# neopixelwordclock.net
KiCad netlist of a schematic drawn in EAGLE
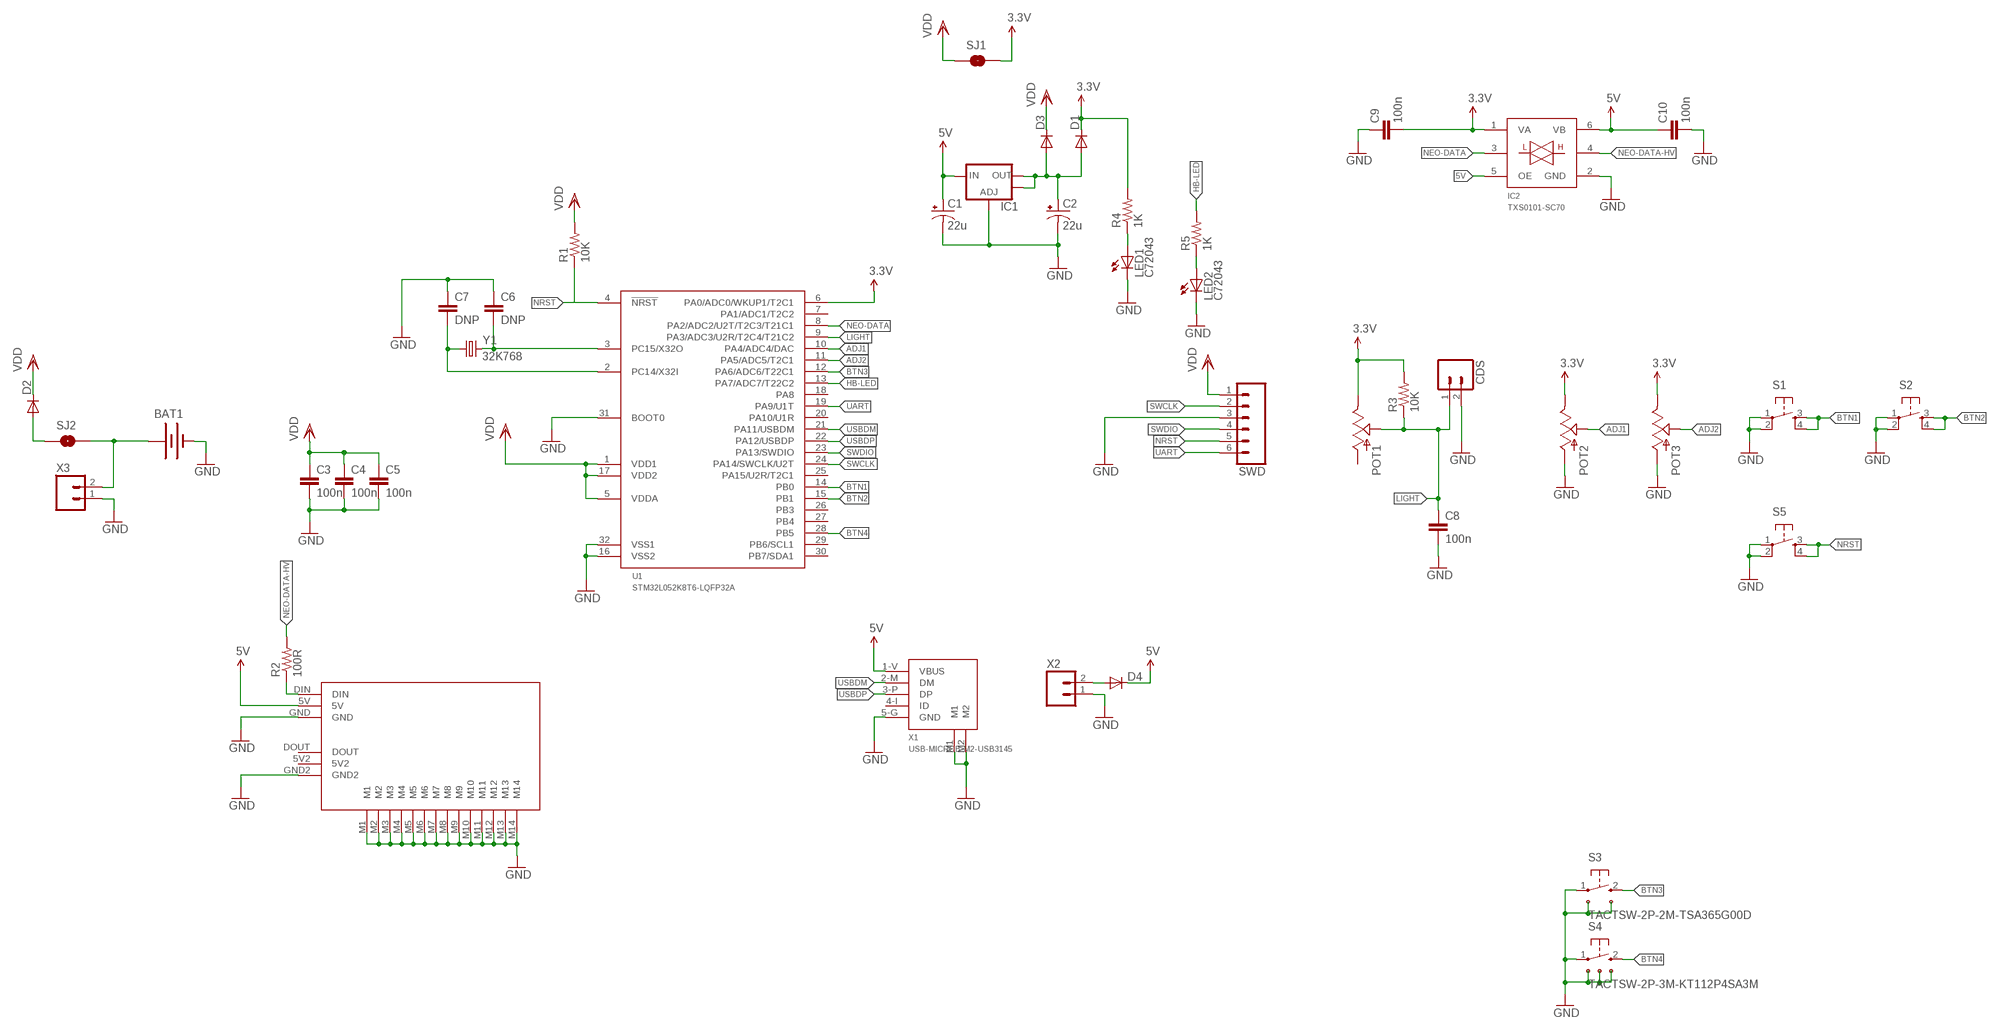
[diagram p0: schematic, sheet 1]

(export (version "E")
  (design (tool "Eeschema 10.0.6"))
  (components
    (comp (ref "BAT1")
      (value "BATTERY-JLC")
      (footprint "eagle-import:BATT-COIN-CR2032-BS-6-1")
      (libsource (lib "eagle-import") (part "BATTERY-JLC"))
    )
    (comp (ref "C1")
      (value "22u")
      (footprint "eagle-import:EIA3528")
      (libsource (lib "eagle-import") (part "CAP_POL3528"))
    )
    (comp (ref "C2")
      (value "22u")
      (footprint "eagle-import:EIA3528")
      (libsource (lib "eagle-import") (part "CAP_POL3528"))
    )
    (comp (ref "C3")
      (value "100n")
      (footprint "eagle-import:0603-CAP")
      (libsource (lib "eagle-import") (part "CAP0603-CAP"))
    )
    (comp (ref "C4")
      (value "100n")
      (footprint "eagle-import:0603-CAP")
      (libsource (lib "eagle-import") (part "CAP0603-CAP"))
    )
    (comp (ref "C5")
      (value "100n")
      (footprint "eagle-import:0603-CAP")
      (libsource (lib "eagle-import") (part "CAP0603-CAP"))
    )
    (comp (ref "C6")
      (value "DNP")
      (footprint "eagle-import:0603-CAP")
      (libsource (lib "eagle-import") (part "CAP0603-CAP"))
    )
    (comp (ref "C7")
      (value "DNP")
      (footprint "eagle-import:0603-CAP")
      (libsource (lib "eagle-import") (part "CAP0603-CAP"))
    )
    (comp (ref "C8")
      (value "100n")
      (footprint "eagle-import:0603-CAP")
      (libsource (lib "eagle-import") (part "CAP0603-CAP"))
    )
    (comp (ref "C9")
      (value "100n")
      (footprint "eagle-import:0603-CAP")
      (libsource (lib "eagle-import") (part "CAP0603-CAP"))
    )
    (comp (ref "C10")
      (value "100n")
      (footprint "eagle-import:0603-CAP")
      (libsource (lib "eagle-import") (part "CAP0603-CAP"))
    )
    (comp (ref "CDS")
      (value "M02PTH")
      (footprint "eagle-import:1X02")
      (libsource (lib "eagle-import") (part "M02PTH"))
    )
    (comp (ref "D1")
      (value "DIODESOD")
      (footprint "eagle-import:SOD-323")
      (libsource (lib "eagle-import") (part "DIODESOD"))
    )
    (comp (ref "D2")
      (value "DIODESOD")
      (footprint "eagle-import:SOD-323")
      (libsource (lib "eagle-import") (part "DIODESOD"))
    )
    (comp (ref "D3")
      (value "DIODESOD")
      (footprint "eagle-import:SOD-323")
      (libsource (lib "eagle-import") (part "DIODESOD"))
    )
    (comp (ref "D4")
      (value "DIODESMA")
      (footprint "eagle-import:SMA-DIODE")
      (libsource (lib "eagle-import") (part "DIODESMA"))
    )
    (comp (ref "IC1")
      (value "V_REG_LM1117SOT223")
      (footprint "eagle-import:SOT223")
      (libsource (lib "eagle-import") (part "V_REG_LM1117SOT223"))
    )
    (comp (ref "IC2")
      (value "TXS0101-SC70")
      (footprint "eagle-import:SC70-6")
      (libsource (lib "eagle-import") (part "TXS0101-SC70"))
    )
    (comp (ref "LED1")
      (value "C72043")
      (footprint "eagle-import:LED-0603")
      (libsource (lib "eagle-import") (part "LED0603"))
    )
    (comp (ref "LED2")
      (value "C72043")
      (footprint "eagle-import:LED-0603")
      (libsource (lib "eagle-import") (part "LED0603"))
    )
    (comp (ref "POT1")
      (value "POT-SMD-A")
      (footprint "eagle-import:POT-SMD")
      (libsource (lib "eagle-import") (part "POT-SMD-A"))
    )
    (comp (ref "POT2")
      (value "POT-SMD-A")
      (footprint "eagle-import:POT-SMD")
      (libsource (lib "eagle-import") (part "POT-SMD-A"))
    )
    (comp (ref "POT3")
      (value "POT-SMD-A")
      (footprint "eagle-import:POT-SMD")
      (libsource (lib "eagle-import") (part "POT-SMD-A"))
    )
    (comp (ref "R1")
      (value "10K")
      (footprint "eagle-import:0603-RES")
      (libsource (lib "eagle-import") (part "RESISTOR0603-RES"))
    )
    (comp (ref "R2")
      (value "100R")
      (footprint "eagle-import:0603-RES")
      (libsource (lib "eagle-import") (part "RESISTOR0603-RES"))
    )
    (comp (ref "R3")
      (value "10K")
      (footprint "eagle-import:0603-RES")
      (libsource (lib "eagle-import") (part "RESISTOR0603-RES"))
    )
    (comp (ref "R4")
      (value "1K")
      (footprint "eagle-import:0603-RES")
      (libsource (lib "eagle-import") (part "RESISTOR0603-RES"))
    )
    (comp (ref "R5")
      (value "1K")
      (footprint "eagle-import:0603-RES")
      (libsource (lib "eagle-import") (part "RESISTOR0603-RES"))
    )
    (comp (ref "S1")
      (value "TAC_SWITCHSMD")
      (footprint "eagle-import:TACTILE_SWITCH_SMD")
      (libsource (lib "eagle-import") (part "TAC_SWITCHSMD"))
    )
    (comp (ref "S2")
      (value "TAC_SWITCHSMD")
      (footprint "eagle-import:TACTILE_SWITCH_SMD")
      (libsource (lib "eagle-import") (part "TAC_SWITCHSMD"))
    )
    (comp (ref "S3")
      (value "TACTSW-2P-2M-TSA365G00D")
      (footprint "eagle-import:TACTSW-SMD-SIDE-TSA365G00D")
      (libsource (lib "eagle-import") (part "TACTSW-2P-2M-TSA365G00D"))
    )
    (comp (ref "S4")
      (value "TACTSW-2P-3M-KT112P4SA3M")
      (footprint "eagle-import:TACTSW-SMD-SIDE-KT11P4SA3M")
      (libsource (lib "eagle-import") (part "TACTSW-2P-3M-KT112P4SA3M"))
    )
    (comp (ref "S5")
      (value "TAC_SWITCHSMD")
      (footprint "eagle-import:TACTILE_SWITCH_SMD")
      (libsource (lib "eagle-import") (part "TAC_SWITCHSMD"))
    )
    (comp (ref "SJ1")
      (value "SOLDERJUMPERNO")
      (footprint "eagle-import:SJ_2S-NO")
      (libsource (lib "eagle-import") (part "SOLDERJUMPERNO"))
    )
    (comp (ref "SJ2")
      (value "SOLDERJUMPER-BIG")
      (footprint "eagle-import:SJ_2S_BIG")
      (libsource (lib "eagle-import") (part "SOLDERJUMPER-BIG"))
    )
    (comp (ref "SWD")
      (value "M06FEMALE_LOCK")
      (footprint "eagle-import:1X06_FEMALE_LOCK.010")
      (libsource (lib "eagle-import") (part "M06FEMALE_LOCK"))
    )
    (comp (ref "U$1")
      (value "PCB-OUTLINE")
      (footprint "eagle-import:PCB-OUTLINE")
      (libsource (lib "eagle-import") (part "PCB-OUTLINE"))
    )
    (comp (ref "U1")
      (value "STM32L052K8T6-LQFP32A")
      (footprint "eagle-import:LQFP32")
      (libsource (lib "eagle-import") (part "STM32L052K8T6-LQFP32A"))
    )
    (comp (ref "X1")
      (value "USB-MICROB-M2-USB3145")
      (footprint "eagle-import:USBMICROBVERT-USB3145")
      (libsource (lib "eagle-import") (part "USB-MICROB-M2-USB3145"))
    )
    (comp (ref "X2")
      (value "M02-JST-2-PTH-NO_SILK")
      (footprint "eagle-import:JST-2-PTH-NS")
      (libsource (lib "eagle-import") (part "M02-JST-2-PTH-NO_SILK"))
    )
    (comp (ref "X3")
      (value "M02-JST-2-PTH-NO_SILK")
      (footprint "eagle-import:JST-2-PTH-NS")
      (libsource (lib "eagle-import") (part "M02-JST-2-PTH-NO_SILK"))
    )
    (comp (ref "Y1")
      (value "32K768")
      (footprint "eagle-import:XTAL-3.2X1.5")
      (libsource (lib "eagle-import") (part "CRYSTAL-3.2X1.5"))
    )
  )
  (nets
    (net (code "1") (name "3.3V") (class "Default")
      (node (ref "C9") (pin "2") (pinfunction "2_2") (pintype "passive"))
      (node (ref "D1") (pin "1") (pinfunction "C_1") (pintype "passive"))
      (node (ref "IC2") (pin "1") (pinfunction "VA_1") (pintype "input"))
      (node (ref "POT1") (pin "A") (pinfunction "B_A") (pintype "passive"))
      (node (ref "POT2") (pin "A") (pinfunction "B_A") (pintype "passive"))
      (node (ref "POT3") (pin "A") (pinfunction "B_A") (pintype "passive"))
      (node (ref "R3") (pin "2") (pinfunction "2_2") (pintype "passive"))
      (node (ref "R4") (pin "2") (pinfunction "2_2") (pintype "passive"))
      (node (ref "SJ1") (pin "2") (pinfunction "2_2") (pintype "passive"))
      (node (ref "U1") (pin "6") (pinfunction "PA0/ADC0/WKUP1/T2C1_6") (pintype "bidirectional"))
    )
    (net (code "2") (name "5V") (class "Default")
      (node (ref "C1") (pin "A") (pinfunction "+_A") (pintype "passive"))
      (node (ref "C10") (pin "1") (pinfunction "1_1") (pintype "passive"))
      (node (ref "D4") (pin "C") (pinfunction "C_C") (pintype "passive"))
      (node (ref "IC1") (pin "3") (pinfunction "IN_3") (pintype "input"))
      (node (ref "IC2") (pin "5") (pinfunction "OE_5") (pintype "input"))
      (node (ref "IC2") (pin "6") (pinfunction "VB_6") (pintype "input"))
      (node (ref "U$1") (pin "5V") (pinfunction "5V_5V") (pintype "bidirectional"))
      (node (ref "X1") (pin "1-V") (pinfunction "VBUS_1-V") (pintype "bidirectional"))
    )
    (net (code "3") (name "ADJ1") (class "Default")
      (node (ref "POT2") (pin "W") (pinfunction "W_W") (pintype "passive"))
      (node (ref "U1") (pin "10") (pinfunction "PA4/ADC4/DAC_10") (pintype "bidirectional"))
    )
    (net (code "4") (name "ADJ2") (class "Default")
      (node (ref "POT3") (pin "W") (pinfunction "W_W") (pintype "passive"))
      (node (ref "U1") (pin "11") (pinfunction "PA5/ADC5/T2C1_11") (pintype "bidirectional"))
    )
    (net (code "5") (name "BTN1") (class "Default")
      (node (ref "S1") (pin "3") (pinfunction "3_3") (pintype "passive"))
      (node (ref "S1") (pin "4") (pinfunction "4_4") (pintype "passive"))
      (node (ref "U1") (pin "14") (pinfunction "PB0_14") (pintype "bidirectional"))
    )
    (net (code "6") (name "BTN2") (class "Default")
      (node (ref "S2") (pin "3") (pinfunction "3_3") (pintype "passive"))
      (node (ref "S2") (pin "4") (pinfunction "4_4") (pintype "passive"))
      (node (ref "U1") (pin "15") (pinfunction "PB1_15") (pintype "bidirectional"))
    )
    (net (code "7") (name "BTN3") (class "Default")
      (node (ref "S3") (pin "2") (pinfunction "2_2") (pintype "passive"))
      (node (ref "U1") (pin "12") (pinfunction "PA6/ADC6/T22C1_12") (pintype "bidirectional"))
    )
    (net (code "8") (name "BTN4") (class "Default")
      (node (ref "S4") (pin "2") (pinfunction "2_2") (pintype "passive"))
      (node (ref "U1") (pin "28") (pinfunction "PB5_28") (pintype "bidirectional"))
    )
    (net (code "9") (name "GND") (class "Default")
      (node (ref "BAT1") (pin "NEG") (pinfunction "-_NEG") (pintype "power_in"))
      (node (ref "C1") (pin "C") (pinfunction "-_C") (pintype "passive"))
      (node (ref "C10") (pin "2") (pinfunction "2_2") (pintype "passive"))
      (node (ref "C2") (pin "C") (pinfunction "-_C") (pintype "passive"))
      (node (ref "C3") (pin "2") (pinfunction "2_2") (pintype "passive"))
      (node (ref "C4") (pin "2") (pinfunction "2_2") (pintype "passive"))
      (node (ref "C5") (pin "2") (pinfunction "2_2") (pintype "passive"))
      (node (ref "C6") (pin "1") (pinfunction "1_1") (pintype "passive"))
      (node (ref "C7") (pin "1") (pinfunction "1_1") (pintype "passive"))
      (node (ref "C8") (pin "2") (pinfunction "2_2") (pintype "passive"))
      (node (ref "C9") (pin "1") (pinfunction "1_1") (pintype "passive"))
      (node (ref "CDS") (pin "2") (pinfunction "2_2") (pintype "passive"))
      (node (ref "IC1") (pin "1") (pinfunction "ADJ_1") (pintype "input"))
      (node (ref "IC2") (pin "2") (pinfunction "GND_2") (pintype "input"))
      (node (ref "LED1") (pin "C") (pinfunction "C_C") (pintype "passive"))
      (node (ref "LED2") (pin "C") (pinfunction "C_C") (pintype "passive"))
      (node (ref "POT2") (pin "B") (pinfunction "A_B") (pintype "passive"))
      (node (ref "POT3") (pin "B") (pinfunction "A_B") (pintype "passive"))
      (node (ref "S1") (pin "1") (pinfunction "1_1") (pintype "passive"))
      (node (ref "S1") (pin "2") (pinfunction "2_2") (pintype "passive"))
      (node (ref "S2") (pin "1") (pinfunction "1_1") (pintype "passive"))
      (node (ref "S2") (pin "2") (pinfunction "2_2") (pintype "passive"))
      (node (ref "S3") (pin "1") (pinfunction "1_1") (pintype "passive"))
      (node (ref "S3") (pin "M1") (pinfunction "M1_M1") (pintype "bidirectional"))
      (node (ref "S3") (pin "M2") (pinfunction "M2_M2") (pintype "bidirectional"))
      (node (ref "S4") (pin "1") (pinfunction "1_1") (pintype "passive"))
      (node (ref "S4") (pin "M1") (pinfunction "M1_M1") (pintype "bidirectional"))
      (node (ref "S4") (pin "M2") (pinfunction "M2_M2") (pintype "bidirectional"))
      (node (ref "S4") (pin "M3") (pinfunction "M3_M3") (pintype "bidirectional"))
      (node (ref "S5") (pin "1") (pinfunction "1_1") (pintype "passive"))
      (node (ref "S5") (pin "2") (pinfunction "2_2") (pintype "passive"))
      (node (ref "SWD") (pin "3") (pinfunction "3_3") (pintype "passive"))
      (node (ref "U$1") (pin "GND") (pinfunction "GND_GND") (pintype "bidirectional"))
      (node (ref "U$1") (pin "GND2") (pinfunction "GND2_GND2") (pintype "bidirectional"))
      (node (ref "U$1") (pin "M1") (pinfunction "M1_M1") (pintype "bidirectional"))
      (node (ref "U$1") (pin "M10") (pinfunction "M10_M10") (pintype "bidirectional"))
      (node (ref "U$1") (pin "M11") (pinfunction "M11_M11") (pintype "bidirectional"))
      (node (ref "U$1") (pin "M12") (pinfunction "M12_M12") (pintype "bidirectional"))
      (node (ref "U$1") (pin "M13") (pinfunction "M13_M13") (pintype "bidirectional"))
      (node (ref "U$1") (pin "M14") (pinfunction "M14_M14") (pintype "bidirectional"))
      (node (ref "U$1") (pin "M2") (pinfunction "M2_M2") (pintype "bidirectional"))
      (node (ref "U$1") (pin "M3") (pinfunction "M3_M3") (pintype "bidirectional"))
      (node (ref "U$1") (pin "M4") (pinfunction "M4_M4") (pintype "bidirectional"))
      (node (ref "U$1") (pin "M5") (pinfunction "M5_M5") (pintype "bidirectional"))
      (node (ref "U$1") (pin "M6") (pinfunction "M6_M6") (pintype "bidirectional"))
      (node (ref "U$1") (pin "M7") (pinfunction "M7_M7") (pintype "bidirectional"))
      (node (ref "U$1") (pin "M8") (pinfunction "M8_M8") (pintype "bidirectional"))
      (node (ref "U$1") (pin "M9") (pinfunction "M9_M9") (pintype "bidirectional"))
      (node (ref "U1") (pin "16") (pinfunction "VSS2_16") (pintype "input"))
      (node (ref "U1") (pin "31") (pinfunction "BOOT0_31") (pintype "input"))
      (node (ref "U1") (pin "32") (pinfunction "VSS1_32") (pintype "input"))
      (node (ref "X1") (pin "5-G") (pinfunction "GND_5-G") (pintype "bidirectional"))
      (node (ref "X1") (pin "M1") (pinfunction "M1_M1") (pintype "bidirectional"))
      (node (ref "X1") (pin "M2") (pinfunction "M2_M2") (pintype "bidirectional"))
      (node (ref "X2") (pin "1") (pinfunction "1_1") (pintype "passive"))
      (node (ref "X3") (pin "1") (pinfunction "1_1") (pintype "passive"))
    )
    (net (code "10") (name "HB-LED") (class "Default")
      (node (ref "R5") (pin "2") (pinfunction "2_2") (pintype "passive"))
      (node (ref "U1") (pin "13") (pinfunction "PA7/ADC7/T22C2_13") (pintype "bidirectional"))
    )
    (net (code "11") (name "LIGHT") (class "Default")
      (node (ref "C8") (pin "1") (pinfunction "1_1") (pintype "passive"))
      (node (ref "CDS") (pin "1") (pinfunction "1_1") (pintype "passive"))
      (node (ref "POT1") (pin "W") (pinfunction "W_W") (pintype "passive"))
      (node (ref "R3") (pin "1") (pinfunction "1_1") (pintype "passive"))
      (node (ref "U1") (pin "9") (pinfunction "PA3/ADC3/U2R/T2C4/T21C2_9") (pintype "bidirectional"))
    )
    (net (code "12") (name "NEO-DATA") (class "Default")
      (node (ref "IC2") (pin "3") (pinfunction "A_3") (pintype "bidirectional"))
      (node (ref "U1") (pin "8") (pinfunction "PA2/ADC2/U2T/T2C3/T21C1_8") (pintype "bidirectional"))
    )
    (net (code "13") (name "NEO-DATA-HV") (class "Default")
      (node (ref "IC2") (pin "4") (pinfunction "B_4") (pintype "bidirectional"))
      (node (ref "R2") (pin "2") (pinfunction "2_2") (pintype "passive"))
    )
    (net (code "14") (name "NRST") (class "Default")
      (node (ref "R1") (pin "1") (pinfunction "1_1") (pintype "passive"))
      (node (ref "S5") (pin "3") (pinfunction "3_3") (pintype "passive"))
      (node (ref "S5") (pin "4") (pinfunction "4_4") (pintype "passive"))
      (node (ref "SWD") (pin "5") (pinfunction "5_5") (pintype "passive"))
      (node (ref "U1") (pin "4") (pinfunction "~{NRST}_4") (pintype "input"))
    )
    (net (code "15") (name "Net-(BAT1-+)") (class "Default")
      (node (ref "BAT1") (pin "POS") (pinfunction "+_POS") (pintype "power_in"))
      (node (ref "SJ2") (pin "2") (pinfunction "2_2") (pintype "passive"))
      (node (ref "X3") (pin "2") (pinfunction "2_2") (pintype "passive"))
    )
    (net (code "16") (name "Net-(C2-+)") (class "Default")
      (node (ref "C2") (pin "A") (pinfunction "+_A") (pintype "passive"))
      (node (ref "D1") (pin "2") (pinfunction "A_2") (pintype "passive"))
      (node (ref "D3") (pin "2") (pinfunction "A_2") (pintype "passive"))
      (node (ref "IC1") (pin "2") (pinfunction "OUT_2") (pintype "output"))
      (node (ref "IC1") (pin "4") (pinfunction "OUT_4") (pintype "output"))
    )
    (net (code "17") (name "Net-(D2-A)") (class "Default")
      (node (ref "D2") (pin "2") (pinfunction "A_2") (pintype "passive"))
      (node (ref "SJ2") (pin "1") (pinfunction "1_1") (pintype "passive"))
    )
    (net (code "18") (name "Net-(D4-PadA)") (class "Default")
      (node (ref "D4") (pin "A") (pinfunction "A_A") (pintype "passive"))
      (node (ref "X2") (pin "2") (pinfunction "2_2") (pintype "passive"))
    )
    (net (code "19") (name "Net-(LED1-PadA)") (class "Default")
      (node (ref "LED1") (pin "A") (pinfunction "A_A") (pintype "passive"))
      (node (ref "R4") (pin "1") (pinfunction "1_1") (pintype "passive"))
    )
    (net (code "20") (name "Net-(LED2-PadA)") (class "Default")
      (node (ref "LED2") (pin "A") (pinfunction "A_A") (pintype "passive"))
      (node (ref "R5") (pin "1") (pinfunction "1_1") (pintype "passive"))
    )
    (net (code "21") (name "Net-(R2-Pad1)") (class "Default")
      (node (ref "R2") (pin "1") (pinfunction "1_1") (pintype "passive"))
      (node (ref "U$1") (pin "DIN") (pinfunction "DIN_DIN") (pintype "bidirectional"))
    )
    (net (code "22") (name "Net-(U1-PC14{slash}X32I)") (class "Default")
      (node (ref "C7") (pin "2") (pinfunction "2_2") (pintype "passive"))
      (node (ref "U1") (pin "2") (pinfunction "PC14/X32I_2") (pintype "bidirectional"))
      (node (ref "Y1") (pin "1") (pinfunction "1_1") (pintype "passive"))
    )
    (net (code "23") (name "Net-(U1-PC15{slash}X32O)") (class "Default")
      (node (ref "C6") (pin "2") (pinfunction "2_2") (pintype "passive"))
      (node (ref "U1") (pin "3") (pinfunction "PC15/X32O_3") (pintype "bidirectional"))
      (node (ref "Y1") (pin "2") (pinfunction "2_2") (pintype "passive"))
    )
    (net (code "24") (name "SWCLK") (class "Default")
      (node (ref "SWD") (pin "2") (pinfunction "2_2") (pintype "passive"))
      (node (ref "U1") (pin "24") (pinfunction "PA14/SWCLK/U2T_24") (pintype "bidirectional"))
    )
    (net (code "25") (name "SWDIO") (class "Default")
      (node (ref "SWD") (pin "4") (pinfunction "4_4") (pintype "passive"))
      (node (ref "U1") (pin "23") (pinfunction "PA13/SWDIO_23") (pintype "bidirectional"))
    )
    (net (code "26") (name "UART") (class "Default")
      (node (ref "SWD") (pin "6") (pinfunction "6_6") (pintype "passive"))
      (node (ref "U1") (pin "19") (pinfunction "PA9/U1T_19") (pintype "bidirectional"))
    )
    (net (code "27") (name "USBDM") (class "Default")
      (node (ref "U1") (pin "21") (pinfunction "PA11/USBDM_21") (pintype "bidirectional"))
      (node (ref "X1") (pin "2-M") (pinfunction "DM_2-M") (pintype "bidirectional"))
    )
    (net (code "28") (name "USBDP") (class "Default")
      (node (ref "U1") (pin "22") (pinfunction "PA12/USBDP_22") (pintype "bidirectional"))
      (node (ref "X1") (pin "3-P") (pinfunction "DP_3-P") (pintype "bidirectional"))
    )
    (net (code "29") (name "VDD") (class "Default")
      (node (ref "C3") (pin "1") (pinfunction "1_1") (pintype "passive"))
      (node (ref "C4") (pin "1") (pinfunction "1_1") (pintype "passive"))
      (node (ref "C5") (pin "1") (pinfunction "1_1") (pintype "passive"))
      (node (ref "D2") (pin "1") (pinfunction "C_1") (pintype "passive"))
      (node (ref "D3") (pin "1") (pinfunction "C_1") (pintype "passive"))
      (node (ref "R1") (pin "2") (pinfunction "2_2") (pintype "passive"))
      (node (ref "SJ1") (pin "1") (pinfunction "1_1") (pintype "passive"))
      (node (ref "SWD") (pin "1") (pinfunction "1_1") (pintype "passive"))
      (node (ref "U1") (pin "1") (pinfunction "VDD1_1") (pintype "input"))
      (node (ref "U1") (pin "17") (pinfunction "VDD2_17") (pintype "input"))
      (node (ref "U1") (pin "5") (pinfunction "VDDA_5") (pintype "input"))
    )
    (net (code "30") (name "unconnected-(POT1-A-PadB)") (class "Default")
      (node (ref "POT1") (pin "B") (pinfunction "A_B") (pintype "passive"))
    )
    (net (code "31") (name "unconnected-(U$1-Pad5V2)") (class "Default")
      (node (ref "U$1") (pin "5V2") (pinfunction "5V2_5V2") (pintype "bidirectional"))
    )
    (net (code "32") (name "unconnected-(U$1-PadDOUT)") (class "Default")
      (node (ref "U$1") (pin "DOUT") (pinfunction "DOUT_DOUT") (pintype "bidirectional"))
    )
    (net (code "33") (name "unconnected-(U1-PA1{slash}ADC1{slash}T2C2-Pad7)") (class "Default")
      (node (ref "U1") (pin "7") (pinfunction "PA1/ADC1/T2C2_7") (pintype "bidirectional"))
    )
    (net (code "34") (name "unconnected-(U1-PA8-Pad18)") (class "Default")
      (node (ref "U1") (pin "18") (pinfunction "PA8_18") (pintype "bidirectional"))
    )
    (net (code "35") (name "unconnected-(U1-PA10{slash}U1R-Pad20)") (class "Default")
      (node (ref "U1") (pin "20") (pinfunction "PA10/U1R_20") (pintype "bidirectional"))
    )
    (net (code "36") (name "unconnected-(U1-PA15{slash}U2R{slash}T2C1-Pad25)") (class "Default")
      (node (ref "U1") (pin "25") (pinfunction "PA15/U2R/T2C1_25") (pintype "bidirectional"))
    )
    (net (code "37") (name "unconnected-(U1-PB3-Pad26)") (class "Default")
      (node (ref "U1") (pin "26") (pinfunction "PB3_26") (pintype "bidirectional"))
    )
    (net (code "38") (name "unconnected-(U1-PB4-Pad27)") (class "Default")
      (node (ref "U1") (pin "27") (pinfunction "PB4_27") (pintype "bidirectional"))
    )
    (net (code "39") (name "unconnected-(U1-PB6{slash}SCL1-Pad29)") (class "Default")
      (node (ref "U1") (pin "29") (pinfunction "PB6/SCL1_29") (pintype "bidirectional"))
    )
    (net (code "40") (name "unconnected-(U1-PB7{slash}SDA1-Pad30)") (class "Default")
      (node (ref "U1") (pin "30") (pinfunction "PB7/SDA1_30") (pintype "bidirectional"))
    )
    (net (code "41") (name "unconnected-(X1-ID-Pad4-I)") (class "Default")
      (node (ref "X1") (pin "4-I") (pinfunction "ID_4-I") (pintype "bidirectional"))
    )
  )
)
